# 1_Overview.net
KiCad netlist of a schematic drawn in Altium Designer
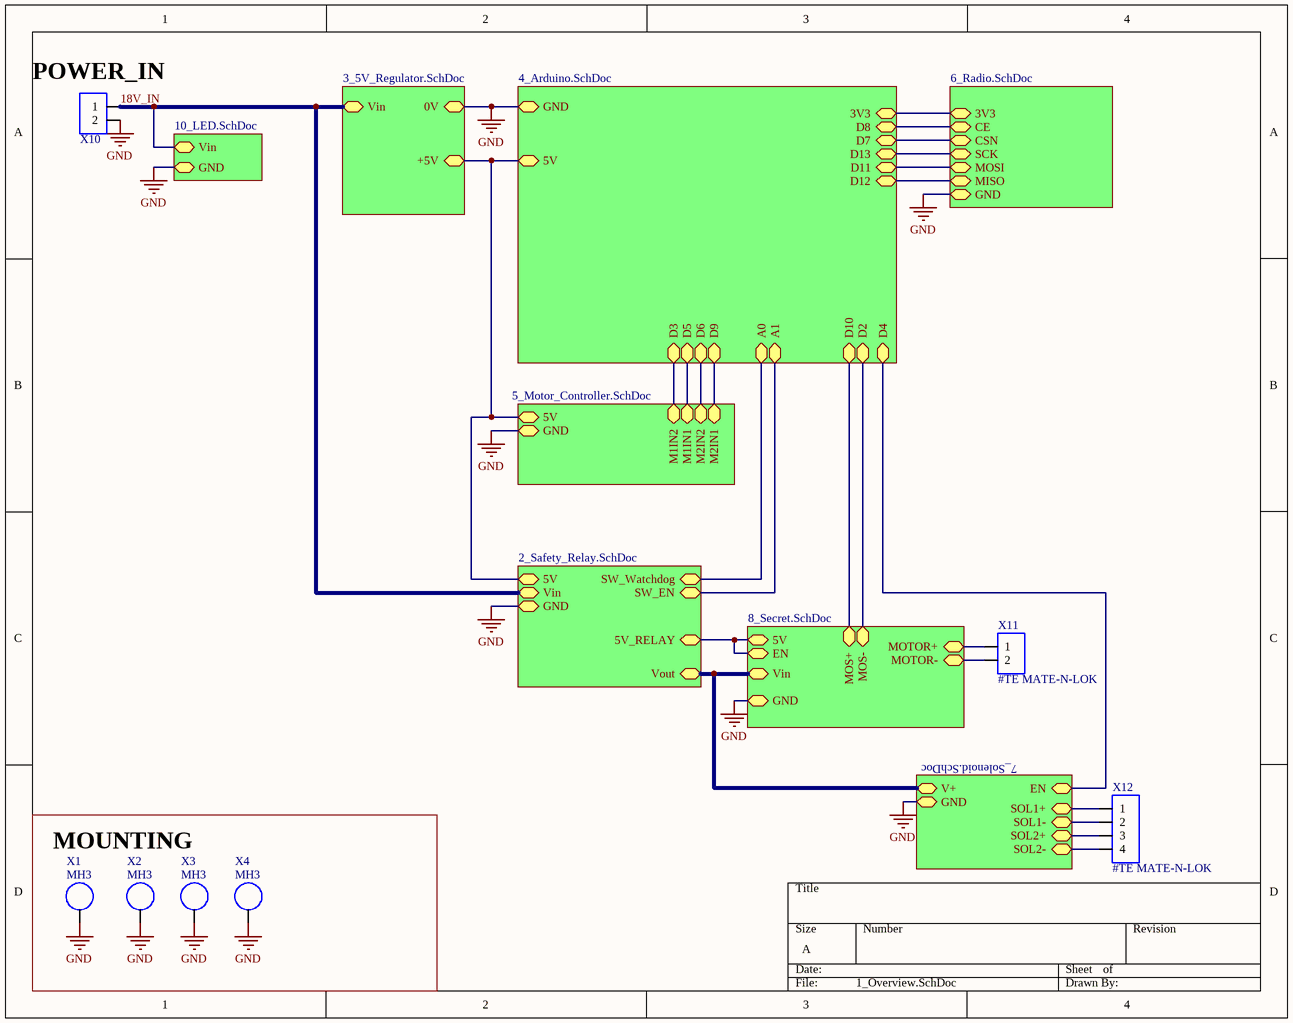
[diagram p0: 1_Overview.SchDoc]

(export (version "E")
  (design (tool "Eeschema 10.0.6"))
  (components
    (comp (ref "X1")
      (value "MH3")
      (footprint "MH-M3-SEMS-6.7-3.6-Vias-Unplated")
      (description "MOUNTING HOLE")
      (fields (field (name "CHECKEDBY") "vhq"))
      (libsource (lib "SVN_BOMGEN_Database_2014") (part "MOUNTING-HOLE"))
    )
    (comp (ref "X2")
      (value "MH3")
      (footprint "MH-M3-SEMS-6.7-3.6-Vias-Unplated")
      (description "MOUNTING HOLE")
      (fields (field (name "CHECKEDBY") "vhq"))
      (libsource (lib "SVN_BOMGEN_Database_2014") (part "MOUNTING-HOLE"))
    )
    (comp (ref "X3")
      (value "MH3")
      (footprint "MH-M3-SEMS-6.7-3.6-Vias-Unplated")
      (description "MOUNTING HOLE")
      (fields (field (name "CHECKEDBY") "vhq"))
      (libsource (lib "SVN_BOMGEN_Database_2014") (part "MOUNTING-HOLE"))
    )
    (comp (ref "X4")
      (value "MH3")
      (footprint "MH-M3-SEMS-6.7-3.6-Vias-Unplated")
      (description "MOUNTING HOLE")
      (fields (field (name "CHECKEDBY") "vhq"))
      (libsource (lib "SVN_BOMGEN_Database_2014") (part "MOUNTING-HOLE"))
    )
    (comp (ref "X10")
      (value "CONN2_12AWG_Hole")
      (footprint "2_Wire_12AWG")
      (fields (field (name "CHECKEDBY") "-"))
      (libsource (lib "Sumo_2016") (part "CONN2_12AWG_Hole"))
    )
    (comp (ref "X11")
      (value "#TE MATE-N-LOK")
      (footprint "HDR-6.35-2-MATENLOK")
      (description "Connector 2 pin general")
      (fields
        (field (name "MANUFACTURER") "TYCO")
        (field (name "PARTNUMBER") "350786-1")
        (field (name "CHECKEDBY") "LGG")
      )
      (libsource (lib "SVN_BOMGEN_Database_2014") (part "CONN2"))
    )
    (comp (ref "X12")
      (value "#TE MATE-N-LOK")
      (footprint "HDR-3.0-4X1-MICROMATENLOK-VERT")
      (description "Connector 4 pin general")
      (fields
        (field (name "MANUFACTURER") "TE Connectivity")
        (field (name "PARTNUMBER") "2-1445094-4")
        (field (name "CHECKEDBY") "vhq")
      )
      (libsource (lib "SVN_BOMGEN_Database_2014") (part "CONN4"))
    )
  )
  (nets
    (net (code "4") (name "/18V_IN") (class "Default")
      (node (ref "X10") (pin "1") (pinfunction "1_1") (pintype "passive"))
    )
    (net (code "19") (name "/MOTOR+") (class "Default")
      (node (ref "X11") (pin "1") (pinfunction "1_1") (pintype "passive"))
    )
    (net (code "20") (name "/MOTOR-") (class "Default")
      (node (ref "X11") (pin "2") (pinfunction "2_2") (pintype "passive"))
    )
    (net (code "21") (name "/SOL1+") (class "Default")
      (node (ref "X12") (pin "1") (pinfunction "1_1") (pintype "passive"))
    )
    (net (code "22") (name "/SOL1-") (class "Default")
      (node (ref "X12") (pin "2") (pinfunction "2_2") (pintype "passive"))
    )
    (net (code "23") (name "/SOL2+") (class "Default")
      (node (ref "X12") (pin "3") (pinfunction "3_3") (pintype "passive"))
    )
    (net (code "24") (name "/SOL2-") (class "Default")
      (node (ref "X12") (pin "4") (pinfunction "4_4") (pintype "passive"))
    )
    (net (code "26") (name "GND") (class "Default")
      (node (ref "X1") (pin "1") (pinfunction "1_1") (pintype "passive"))
      (node (ref "X10") (pin "2") (pinfunction "2_2") (pintype "passive"))
      (node (ref "X2") (pin "1") (pinfunction "1_1") (pintype "passive"))
      (node (ref "X3") (pin "1") (pinfunction "1_1") (pintype "passive"))
      (node (ref "X4") (pin "1") (pinfunction "1_1") (pintype "passive"))
    )
  )
)
